# Microcontroller_Schematic_404.net
KiCad netlist of a schematic drawn in Altium Designer
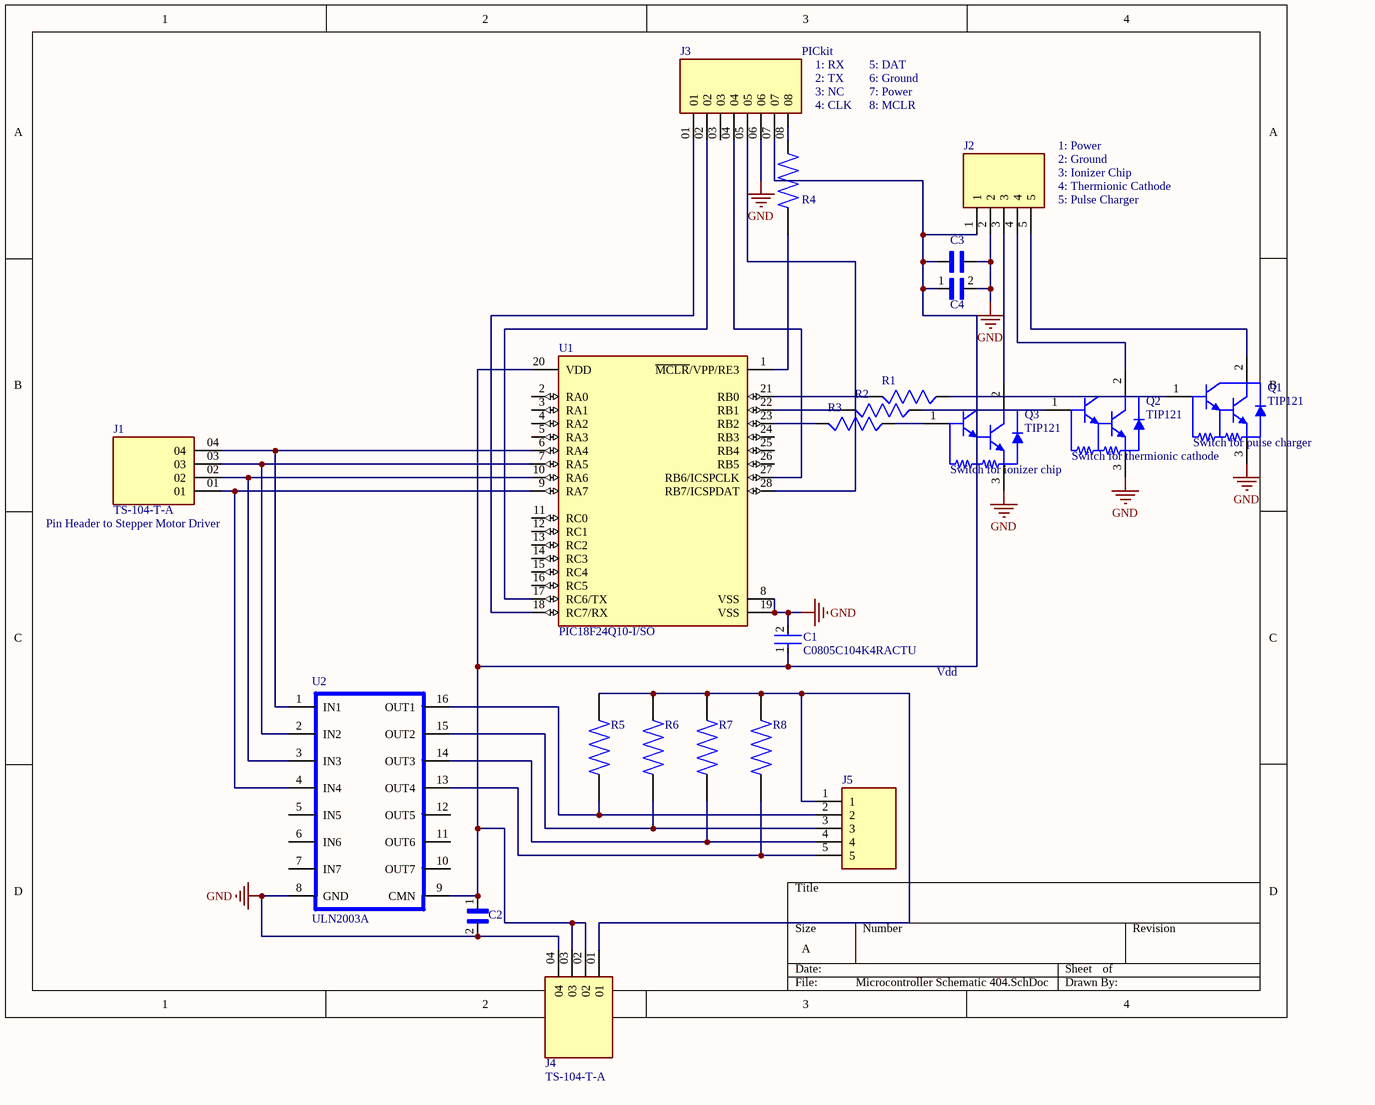
[diagram p0: Microcontroller Schematic 404.SchDoc]

(export (version "E")
  (design (tool "Eeschema 10.0.6"))
  (components
    (comp (ref "C1")
      (value "C0805C104K4RACTU")
      (footprint "CAPC2012X100N")
      (description "CAP CER 0.1UF 16V X7R 0805")
      (fields
        (field (name "OCTOPART") "https://octopart.com/c0805c104k4ractu-kemet-92155")
        (field (name "TOLERANCE") "0.1")
      )
      (libsource (lib "C0805C104K4RAC7800") (part "CMP-2007-00274-2"))
    )
    (comp (ref "C2")
      (value "C0805C104K4RACTU")
      (footprint "CAPC2012X100N")
      (description "10000pF Â±10% 100V Ceramic Capacitor X7R 0805 (2012 Metric)")
      (fields (field (name "MF") "AVX") (field (name "MP") "08051C103KAT2A"))
      (libsource (lib "10nFCAP") (part "08051C103KAT2A"))
    )
    (comp (ref "C3")
      (value "C2012X7S0J106M085AC")
      (footprint "CAPC2012X100N")
      (description "Cap Ceramic 10uF 6.3V X7S 20% SMD 0805 125Â°C Punched Paper T/R")
      (fields (field (name "MF") "{'manufacturer': u'TDK Corporation'}"))
      (libsource (lib "C2012X7S0J106M085AC") (part "C2012X7S0J106M085AC"))
    )
    (comp (ref "C4")
      (value "GRM21BR60J107ME15K")
      (footprint "FP-C0805C-DN-MFG")
      (description "0805 100 uF 6.3 V Â±20% Tolerance X7S Multilayer Ceramic Chip Capacitor")
      (fields (field (name "MF") "Murata Electronics"))
      (libsource (lib "GRM21BR60J107ME15K") (part "GRM21BR60J107ME15K"))
    )
    (comp (ref "J1")
      (value "TS-104-T-A")
      (footprint "SAMTEC_TS-104-T-A")
      (description "TS - Samtec 2.54mm Single Row Machined Terminal Strip - Fast Stock")
      (fields (field (name "MF") "Samtec Inc."))
      (libsource (lib "") (part "TS-104-T-A_1"))
    )
    (comp (ref "J2")
      (value "Comment")
      (footprint "PCBComponent_1")
      (description "5 position terminal block")
      (libsource (lib "282837-5") (part "282837-5"))
    )
    (comp (ref "J3")
      (value "TS-108-X-A-1")
      (footprint "SAMTEC_TS-108-X-A-1:SAMTEC_TS-108-X-A-1")
      (description "TS Series .100 Single Row Screw Machine Terminal Strip")
      (fields (field (name "MP") "TS-108-G-A-1") (field (name "MF") "Samtec"))
      (libsource (lib "TS-108-X-A-1") (part "TS-108-X-A-1"))
    )
    (comp (ref "J4")
      (value "TS-104-T-A")
      (footprint "SAMTEC_TS-104-T-A")
      (description "TS - Samtec 2.54mm Single Row Machined Terminal Strip - Fast Stock")
      (fields (field (name "MF") "Samtec Inc."))
      (libsource (lib "TS-104-T-A") (part "TS-104-T-A"))
    )
    (comp (ref "J5")
      (value "Comment")
      (footprint "SnapEDApcb:TE_440052-5")
      (description "Connector Header Through Hole 5 position 0.098 _2.50mm_")
      (fields (field (name "DIGI-KEY_PART_NUMBER") "A145094-ND") (field (name "MP") "440052-5"))
      (libsource (lib "25SH-B-05-TS") (part "440052-5"))
    )
    (comp (ref "Q1")
      (value "TIP121")
      (footprint "ONSC-TO-220-3-221A-09")
      (description "Plastic Medium-Power, Complementary Silicon Transistor, 3-Pin TO-220, Tube")
      (fields (field (name "MANUFACTURER") "On Semiconductor"))
      (libsource (lib "TIP121") (part "CMP-1047-00128-1"))
    )
    (comp (ref "Q2")
      (value "TIP121")
      (footprint "ONSC-TO-220-3-221A-09")
      (description "Plastic Medium-Power, Complementary Silicon Transistor, 3-Pin TO-220, Tube")
      (fields (field (name "MANUFACTURER") "On Semiconductor"))
      (libsource (lib "TIP121") (part "CMP-1047-00128-1"))
    )
    (comp (ref "Q3")
      (value "TIP121")
      (footprint "ONSC-TO-220-3-221A-09")
      (description "Plastic Medium-Power, Complementary Silicon Transistor, 3-Pin TO-220, Tube")
      (fields (field (name "MANUFACTURER") "On Semiconductor"))
      (libsource (lib "TIP121") (part "CMP-1047-00128-1"))
    )
    (comp (ref "R1")
      (value "RC0805FR-07205RL")
      (footprint "RESC2012X60")
      (description "RC Series 0805 0.125 W 2 kOhms 5% Â±100 ppm/Â°C SMT Thick Film Chip Resistor")
      (fields (field (name "MF") "{'manufacturer': u'YAGEO'}"))
      (libsource (lib "RC0805FR-07205RL") (part "RC0805FR-07205RL"))
    )
    (comp (ref "R2")
      (value "RC0805FR-07205RL")
      (footprint "RESC2012X60")
      (description "RC Series 0805 0.125 W 2 kOhms 5% Â±100 ppm/Â°C SMT Thick Film Chip Resistor")
      (fields (field (name "MF") "{'manufacturer': u'YAGEO'}"))
      (libsource (lib "RC0805FR-07205RL") (part "RC0805FR-07205RL"))
    )
    (comp (ref "R3")
      (value "RC0805FR-07205RL")
      (footprint "RESC2012X60")
      (description "RC Series 0805 0.125 W 2 kOhms 5% Â±100 ppm/Â°C SMT Thick Film Chip Resistor")
      (fields (field (name "MF") "{'manufacturer': u'YAGEO'}"))
      (libsource (lib "RC0805FR-07205RL") (part "RC0805FR-07205RL"))
    )
    (comp (ref "R4")
      (value "RMCF0805JT10K0")
      (footprint "RESC2012X65N:RESC2012X65N")
      (description "10 kOhms Â±5% 0.125W, 1/8W Chip Resistor 0805 (2012 Metric) Automotive AEC-Q200 Thick Film")
      (fields (field (name "MF") "Stackpole Electronics Inc"))
      (libsource (lib "RMCF0805JT10K0") (part "RMCF0805JT10K0"))
    )
    (comp (ref "R5")
      (value "Comment")
      (description "4.7k ohm resistor")
      (libsource (lib "RCC08054K70FKEA") (part "RCC08054K70FKEA"))
    )
    (comp (ref "R6")
      (value "Comment")
      (description "4.7k ohm resistor")
      (libsource (lib "RCC08054K70FKEA") (part "RCC08054K70FKEA"))
    )
    (comp (ref "R7")
      (value "Comment")
      (description "4.7k ohm resistor")
      (libsource (lib "RCC08054K70FKEA") (part "RCC08054K70FKEA"))
    )
    (comp (ref "R8")
      (value "Comment")
      (description "4.7k ohm resistor")
      (libsource (lib "RCC08054K70FKEA") (part "RCC08054K70FKEA"))
    )
    (comp (ref "U1")
      (value "PIC18F24Q10-I/SO")
      (footprint "FP-C04-052-IPC_A")
      (description "IC MCU 8BIT 16KB FLASH 28SOIC")
      (libsource (lib "PIC18F24Q10") (part "CMP-06276-000706-1"))
    )
    (comp (ref "U2")
      (value "ULN2003A")
      (footprint "ULN2003A:DIP762W51P254L1992H425Q16")
      (description "Optocoupler, Photodarlington Output, Dual Channel, High Gain")
      (fields (field (name "MP") "TCED4100"))
      (libsource (lib "ULN2003A") (part "TCED4100"))
    )
  )
  (nets
    (net (code "1") (name "GND") (class "Default")
      (node (ref "C1") (pin "2") (pinfunction "2_2") (pintype "passive"))
      (node (ref "C2") (pin "2") (pinfunction "2_2") (pintype "passive"))
      (node (ref "C3") (pin "2") (pinfunction "2_2") (pintype "passive"))
      (node (ref "C4") (pin "2") (pinfunction "2_2") (pintype "passive"))
      (node (ref "J2") (pin "2") (pinfunction "2_2") (pintype "passive"))
      (node (ref "J3") (pin "06") (pinfunction "06_06") (pintype "passive"))
      (node (ref "J4") (pin "04") (pinfunction "04_04") (pintype "passive"))
      (node (ref "Q1") (pin "3") (pinfunction "E_3") (pintype "passive"))
      (node (ref "Q2") (pin "3") (pinfunction "E_3") (pintype "passive"))
      (node (ref "Q3") (pin "3") (pinfunction "E_3") (pintype "passive"))
      (node (ref "U1") (pin "19") (pinfunction "VSS_19") (pintype "power_in"))
      (node (ref "U1") (pin "8") (pinfunction "VSS_8") (pintype "power_in"))
      (node (ref "U2") (pin "8") (pinfunction "GND_8") (pintype "passive"))
    )
    (net (code "2") (name "Net-(J3-Pad08)") (class "Default")
      (node (ref "J3") (pin "08") (pinfunction "08_08") (pintype "passive"))
      (node (ref "R4") (pin "2") (pinfunction "2_2") (pintype "passive"))
    )
    (net (code "3") (name "Net-(J4-Pad01)") (class "Default")
      (node (ref "J4") (pin "01") (pinfunction "01_01") (pintype "passive"))
      (node (ref "J5") (pin "1") (pinfunction "1_1") (pintype "passive"))
      (node (ref "R5") (pin "2") (pinfunction "2_2") (pintype "passive"))
      (node (ref "R6") (pin "2") (pinfunction "2_2") (pintype "passive"))
      (node (ref "R7") (pin "2") (pinfunction "2_2") (pintype "passive"))
      (node (ref "R8") (pin "2") (pinfunction "2_2") (pintype "passive"))
    )
    (net (code "4") (name "Net-(Q1-B)") (class "Default")
      (node (ref "Q1") (pin "1") (pinfunction "B_1") (pintype "passive"))
      (node (ref "R1") (pin "2") (pinfunction "2_2") (pintype "passive"))
    )
    (net (code "5") (name "Net-(Q1-C)") (class "Default")
      (node (ref "J2") (pin "5") (pinfunction "5_5") (pintype "passive"))
      (node (ref "Q1") (pin "2") (pinfunction "C_2") (pintype "passive"))
    )
    (net (code "6") (name "Net-(Q2-B)") (class "Default")
      (node (ref "Q2") (pin "1") (pinfunction "B_1") (pintype "passive"))
      (node (ref "R2") (pin "2") (pinfunction "2_2") (pintype "passive"))
    )
    (net (code "7") (name "Net-(Q2-C)") (class "Default")
      (node (ref "J2") (pin "4") (pinfunction "4_4") (pintype "passive"))
      (node (ref "Q2") (pin "2") (pinfunction "C_2") (pintype "passive"))
    )
    (net (code "8") (name "Net-(Q3-B)") (class "Default")
      (node (ref "Q3") (pin "1") (pinfunction "B_1") (pintype "passive"))
      (node (ref "R3") (pin "2") (pinfunction "2_2") (pintype "passive"))
    )
    (net (code "9") (name "Net-(Q3-C)") (class "Default")
      (node (ref "J2") (pin "3") (pinfunction "3_3") (pintype "passive"))
      (node (ref "Q3") (pin "2") (pinfunction "C_2") (pintype "passive"))
    )
    (net (code "10") (name "Net-(U1-RA4)") (class "Default")
      (node (ref "J1") (pin "04") (pinfunction "04_04") (pintype "passive"))
      (node (ref "U1") (pin "6") (pinfunction "RA4_6") (pintype "bidirectional"))
      (node (ref "U2") (pin "1") (pinfunction "IN1_1") (pintype "passive"))
    )
    (net (code "11") (name "Net-(U1-RA5)") (class "Default")
      (node (ref "J1") (pin "03") (pinfunction "03_03") (pintype "passive"))
      (node (ref "U1") (pin "7") (pinfunction "RA5_7") (pintype "bidirectional"))
      (node (ref "U2") (pin "2") (pinfunction "IN2_2") (pintype "passive"))
    )
    (net (code "12") (name "Net-(U1-RA6)") (class "Default")
      (node (ref "J1") (pin "02") (pinfunction "02_02") (pintype "passive"))
      (node (ref "U1") (pin "10") (pinfunction "RA6_10") (pintype "bidirectional"))
      (node (ref "U2") (pin "3") (pinfunction "IN3_3") (pintype "passive"))
    )
    (net (code "13") (name "Net-(U1-RA7)") (class "Default")
      (node (ref "J1") (pin "01") (pinfunction "01_01") (pintype "passive"))
      (node (ref "U1") (pin "9") (pinfunction "RA7_9") (pintype "bidirectional"))
      (node (ref "U2") (pin "4") (pinfunction "IN4_4") (pintype "passive"))
    )
    (net (code "14") (name "Net-(U1-RB0)") (class "Default")
      (node (ref "R1") (pin "1") (pinfunction "1_1") (pintype "passive"))
      (node (ref "U1") (pin "21") (pinfunction "RB0_21") (pintype "bidirectional"))
    )
    (net (code "15") (name "Net-(U1-RB1)") (class "Default")
      (node (ref "R2") (pin "1") (pinfunction "1_1") (pintype "passive"))
      (node (ref "U1") (pin "22") (pinfunction "RB1_22") (pintype "bidirectional"))
    )
    (net (code "16") (name "Net-(U1-RB2)") (class "Default")
      (node (ref "R3") (pin "1") (pinfunction "1_1") (pintype "passive"))
      (node (ref "U1") (pin "23") (pinfunction "RB2_23") (pintype "bidirectional"))
    )
    (net (code "17") (name "Net-(U1-RB6{slash}ICSPCLK)") (class "Default")
      (node (ref "J3") (pin "04") (pinfunction "04_04") (pintype "passive"))
      (node (ref "U1") (pin "27") (pinfunction "RB6/ICSPCLK_27") (pintype "bidirectional"))
    )
    (net (code "18") (name "Net-(U1-RB7{slash}ICSPDAT)") (class "Default")
      (node (ref "J3") (pin "05") (pinfunction "05_05") (pintype "passive"))
      (node (ref "U1") (pin "28") (pinfunction "RB7/ICSPDAT_28") (pintype "bidirectional"))
    )
    (net (code "19") (name "Net-(U1-RC6{slash}TX)") (class "Default")
      (node (ref "J3") (pin "02") (pinfunction "02_02") (pintype "passive"))
      (node (ref "U1") (pin "17") (pinfunction "RC6/TX_17") (pintype "bidirectional"))
    )
    (net (code "20") (name "Net-(U1-RC7{slash}RX)") (class "Default")
      (node (ref "J3") (pin "01") (pinfunction "01_01") (pintype "passive"))
      (node (ref "U1") (pin "18") (pinfunction "RC7/RX_18") (pintype "bidirectional"))
    )
    (net (code "21") (name "Net-(U1-VDD)") (class "Default")
      (node (ref "C1") (pin "1") (pinfunction "1_1") (pintype "passive"))
      (node (ref "C2") (pin "1") (pinfunction "1_1") (pintype "passive"))
      (node (ref "C3") (pin "1") (pinfunction "1_1") (pintype "passive"))
      (node (ref "C4") (pin "1") (pinfunction "1_1") (pintype "passive"))
      (node (ref "J2") (pin "1") (pinfunction "1_1") (pintype "passive"))
      (node (ref "J3") (pin "07") (pinfunction "07_07") (pintype "passive"))
      (node (ref "J4") (pin "02") (pinfunction "02_02") (pintype "passive"))
      (node (ref "J4") (pin "03") (pinfunction "03_03") (pintype "passive"))
      (node (ref "U1") (pin "20") (pinfunction "VDD_20") (pintype "power_in"))
      (node (ref "U2") (pin "9") (pinfunction "CMN_9") (pintype "passive"))
    )
    (net (code "22") (name "Net-(U1-~{MCLR}{slash}VPP{slash}RE3)") (class "Default")
      (node (ref "R4") (pin "1") (pinfunction "1_1") (pintype "passive"))
      (node (ref "U1") (pin "1") (pinfunction "~{MCLR}/VPP/RE3_1") (pintype "passive"))
    )
    (net (code "23") (name "Net-(U2-OUT1)") (class "Default")
      (node (ref "J5") (pin "2") (pinfunction "2_2") (pintype "passive"))
      (node (ref "R5") (pin "1") (pinfunction "1_1") (pintype "passive"))
      (node (ref "U2") (pin "16") (pinfunction "OUT1_16") (pintype "passive"))
    )
    (net (code "24") (name "Net-(U2-OUT2)") (class "Default")
      (node (ref "J5") (pin "3") (pinfunction "3_3") (pintype "passive"))
      (node (ref "R6") (pin "1") (pinfunction "1_1") (pintype "passive"))
      (node (ref "U2") (pin "15") (pinfunction "OUT2_15") (pintype "passive"))
    )
    (net (code "25") (name "Net-(U2-OUT3)") (class "Default")
      (node (ref "J5") (pin "4") (pinfunction "4_4") (pintype "passive"))
      (node (ref "R7") (pin "1") (pinfunction "1_1") (pintype "passive"))
      (node (ref "U2") (pin "14") (pinfunction "OUT3_14") (pintype "passive"))
    )
    (net (code "26") (name "Net-(U2-OUT4)") (class "Default")
      (node (ref "J5") (pin "5") (pinfunction "5_5") (pintype "passive"))
      (node (ref "R8") (pin "1") (pinfunction "1_1") (pintype "passive"))
      (node (ref "U2") (pin "13") (pinfunction "OUT4_13") (pintype "passive"))
    )
    (net (code "27") (name "unconnected-(J3-Pad03)") (class "Default")
      (node (ref "J3") (pin "03") (pinfunction "03_03") (pintype "passive"))
    )
    (net (code "28") (name "unconnected-(U1-RA0-Pad2)") (class "Default")
      (node (ref "U1") (pin "2") (pinfunction "RA0_2") (pintype "bidirectional"))
    )
    (net (code "29") (name "unconnected-(U1-RA1-Pad3)") (class "Default")
      (node (ref "U1") (pin "3") (pinfunction "RA1_3") (pintype "bidirectional"))
    )
    (net (code "30") (name "unconnected-(U1-RA2-Pad4)") (class "Default")
      (node (ref "U1") (pin "4") (pinfunction "RA2_4") (pintype "bidirectional"))
    )
    (net (code "31") (name "unconnected-(U1-RA3-Pad5)") (class "Default")
      (node (ref "U1") (pin "5") (pinfunction "RA3_5") (pintype "bidirectional"))
    )
    (net (code "32") (name "unconnected-(U1-RB3-Pad24)") (class "Default")
      (node (ref "U1") (pin "24") (pinfunction "RB3_24") (pintype "bidirectional"))
    )
    (net (code "33") (name "unconnected-(U1-RB4-Pad25)") (class "Default")
      (node (ref "U1") (pin "25") (pinfunction "RB4_25") (pintype "bidirectional"))
    )
    (net (code "34") (name "unconnected-(U1-RB5-Pad26)") (class "Default")
      (node (ref "U1") (pin "26") (pinfunction "RB5_26") (pintype "bidirectional"))
    )
    (net (code "35") (name "unconnected-(U1-RC0-Pad11)") (class "Default")
      (node (ref "U1") (pin "11") (pinfunction "RC0_11") (pintype "bidirectional"))
    )
    (net (code "36") (name "unconnected-(U1-RC1-Pad12)") (class "Default")
      (node (ref "U1") (pin "12") (pinfunction "RC1_12") (pintype "bidirectional"))
    )
    (net (code "37") (name "unconnected-(U1-RC2-Pad13)") (class "Default")
      (node (ref "U1") (pin "13") (pinfunction "RC2_13") (pintype "bidirectional"))
    )
    (net (code "38") (name "unconnected-(U1-RC3-Pad14)") (class "Default")
      (node (ref "U1") (pin "14") (pinfunction "RC3_14") (pintype "bidirectional"))
    )
    (net (code "39") (name "unconnected-(U1-RC4-Pad15)") (class "Default")
      (node (ref "U1") (pin "15") (pinfunction "RC4_15") (pintype "bidirectional"))
    )
    (net (code "40") (name "unconnected-(U1-RC5-Pad16)") (class "Default")
      (node (ref "U1") (pin "16") (pinfunction "RC5_16") (pintype "bidirectional"))
    )
    (net (code "41") (name "unconnected-(U2-IN5-Pad5)") (class "Default")
      (node (ref "U2") (pin "5") (pinfunction "IN5_5") (pintype "passive"))
    )
    (net (code "42") (name "unconnected-(U2-IN6-Pad6)") (class "Default")
      (node (ref "U2") (pin "6") (pinfunction "IN6_6") (pintype "passive"))
    )
    (net (code "43") (name "unconnected-(U2-IN7-Pad7)") (class "Default")
      (node (ref "U2") (pin "7") (pinfunction "IN7_7") (pintype "passive"))
    )
    (net (code "44") (name "unconnected-(U2-OUT5-Pad12)") (class "Default")
      (node (ref "U2") (pin "12") (pinfunction "OUT5_12") (pintype "passive"))
    )
    (net (code "45") (name "unconnected-(U2-OUT6-Pad11)") (class "Default")
      (node (ref "U2") (pin "11") (pinfunction "OUT6_11") (pintype "passive"))
    )
    (net (code "46") (name "unconnected-(U2-OUT7-Pad10)") (class "Default")
      (node (ref "U2") (pin "10") (pinfunction "OUT7_10") (pintype "passive"))
    )
  )
)
